# io.net
KiCad netlist of a schematic drawn in EAGLE
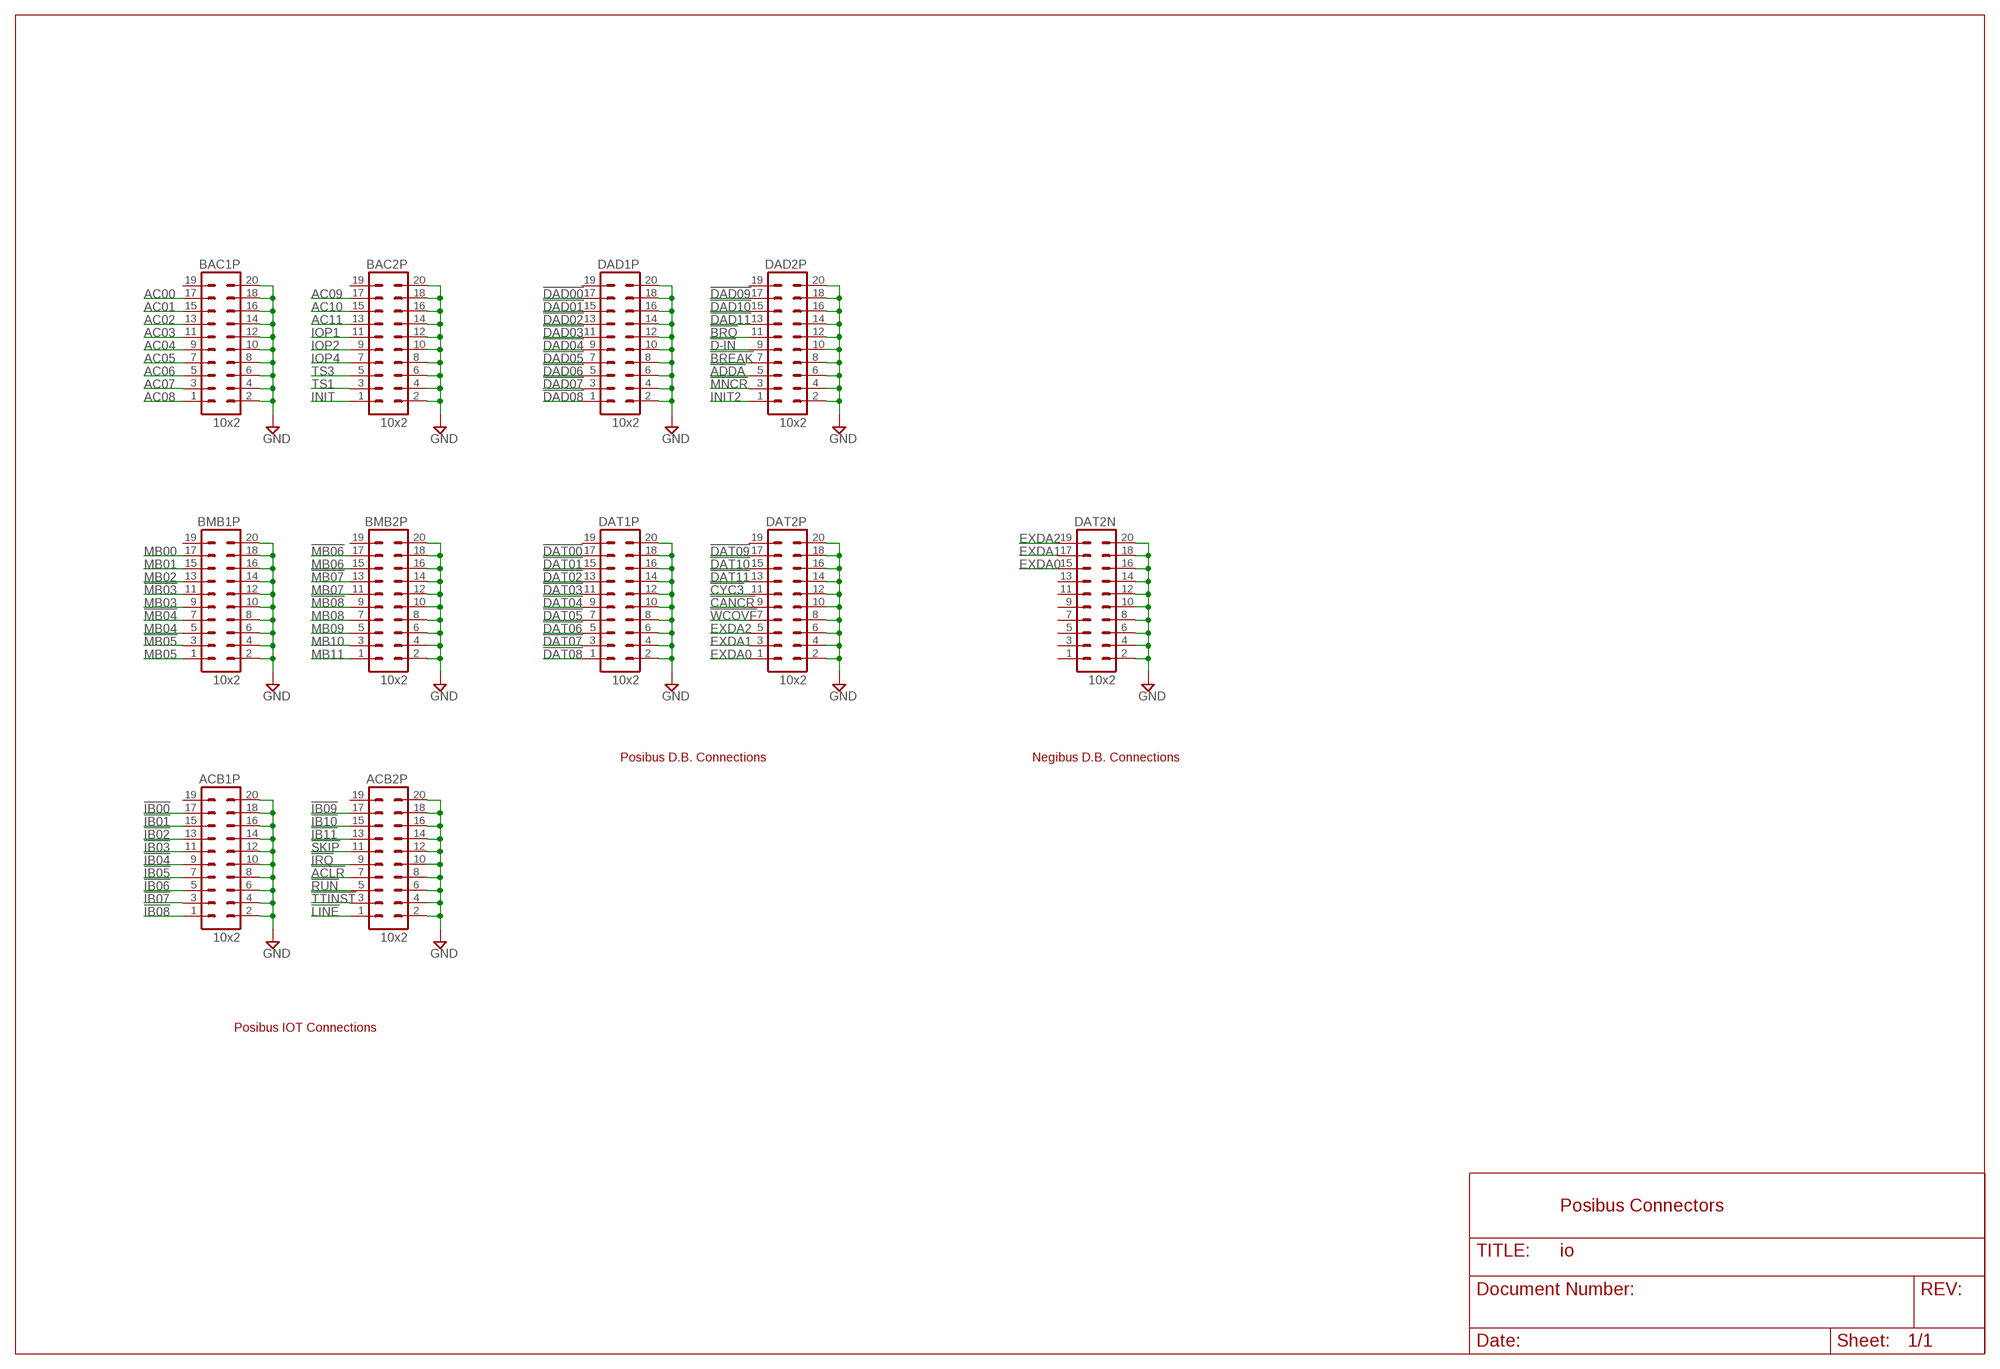
[diagram p0: schematic, sheet 1]

(export (version "E")
  (design (tool "Eeschema 10.0.6"))
  (components
    (comp (ref "ACB1P")
      (value "10x2")
      (footprint "eagle-import:MA10-2")
      (libsource (lib "eagle-import") (part "MA10-2"))
    )
    (comp (ref "ACB2P")
      (value "10x2")
      (footprint "eagle-import:MA10-2")
      (libsource (lib "eagle-import") (part "MA10-2"))
    )
    (comp (ref "BAC1P")
      (value "10x2")
      (footprint "eagle-import:MA10-2")
      (libsource (lib "eagle-import") (part "MA10-2"))
    )
    (comp (ref "BAC2P")
      (value "10x2")
      (footprint "eagle-import:MA10-2")
      (libsource (lib "eagle-import") (part "MA10-2"))
    )
    (comp (ref "BMB1P")
      (value "10x2")
      (footprint "eagle-import:MA10-2")
      (libsource (lib "eagle-import") (part "MA10-2"))
    )
    (comp (ref "BMB2P")
      (value "10x2")
      (footprint "eagle-import:MA10-2")
      (libsource (lib "eagle-import") (part "MA10-2"))
    )
    (comp (ref "DAD1P")
      (value "10x2")
      (footprint "eagle-import:MA10-2")
      (libsource (lib "eagle-import") (part "MA10-2"))
    )
    (comp (ref "DAD2P")
      (value "10x2")
      (footprint "eagle-import:MA10-2")
      (libsource (lib "eagle-import") (part "MA10-2"))
    )
    (comp (ref "DAT1P")
      (value "10x2")
      (footprint "eagle-import:MA10-2")
      (libsource (lib "eagle-import") (part "MA10-2"))
    )
    (comp (ref "DAT2N")
      (value "10x2")
      (footprint "eagle-import:MA10-2")
      (libsource (lib "eagle-import") (part "MA10-2"))
    )
    (comp (ref "DAT2P")
      (value "10x2")
      (footprint "eagle-import:MA10-2")
      (libsource (lib "eagle-import") (part "MA10-2"))
    )
  )
  (nets
    (net (code "1") (name "/AC00") (class "Default")
      (node (ref "BAC1P") (pin "17") (pinfunction "17_17") (pintype "passive"))
    )
    (net (code "2") (name "/AC01") (class "Default")
      (node (ref "BAC1P") (pin "15") (pinfunction "15_15") (pintype "passive"))
    )
    (net (code "3") (name "/AC02") (class "Default")
      (node (ref "BAC1P") (pin "13") (pinfunction "13_13") (pintype "passive"))
    )
    (net (code "4") (name "/AC03") (class "Default")
      (node (ref "BAC1P") (pin "11") (pinfunction "11_11") (pintype "passive"))
    )
    (net (code "5") (name "/AC04") (class "Default")
      (node (ref "BAC1P") (pin "9") (pinfunction "9_9") (pintype "passive"))
    )
    (net (code "6") (name "/AC05") (class "Default")
      (node (ref "BAC1P") (pin "7") (pinfunction "7_7") (pintype "passive"))
    )
    (net (code "7") (name "/AC06") (class "Default")
      (node (ref "BAC1P") (pin "5") (pinfunction "5_5") (pintype "passive"))
    )
    (net (code "8") (name "/AC07") (class "Default")
      (node (ref "BAC1P") (pin "3") (pinfunction "3_3") (pintype "passive"))
    )
    (net (code "9") (name "/AC08") (class "Default")
      (node (ref "BAC1P") (pin "1") (pinfunction "1_1") (pintype "passive"))
    )
    (net (code "10") (name "/AC09") (class "Default")
      (node (ref "BAC2P") (pin "17") (pinfunction "17_17") (pintype "passive"))
    )
    (net (code "11") (name "/AC10") (class "Default")
      (node (ref "BAC2P") (pin "15") (pinfunction "15_15") (pintype "passive"))
    )
    (net (code "12") (name "/AC11") (class "Default")
      (node (ref "BAC2P") (pin "13") (pinfunction "13_13") (pintype "passive"))
    )
    (net (code "13") (name "/EXDA0") (class "Default")
      (node (ref "DAT2N") (pin "15") (pinfunction "15_15") (pintype "passive"))
      (node (ref "DAT2P") (pin "1") (pinfunction "1_1") (pintype "passive"))
    )
    (net (code "14") (name "/EXDA1") (class "Default")
      (node (ref "DAT2N") (pin "17") (pinfunction "17_17") (pintype "passive"))
      (node (ref "DAT2P") (pin "3") (pinfunction "3_3") (pintype "passive"))
    )
    (net (code "15") (name "/EXDA2") (class "Default")
      (node (ref "DAT2N") (pin "19") (pinfunction "19_19") (pintype "passive"))
      (node (ref "DAT2P") (pin "5") (pinfunction "5_5") (pintype "passive"))
    )
    (net (code "16") (name "/INIT") (class "Default")
      (node (ref "BAC2P") (pin "1") (pinfunction "1_1") (pintype "passive"))
    )
    (net (code "17") (name "/INIT2") (class "Default")
      (node (ref "DAD2P") (pin "1") (pinfunction "1_1") (pintype "passive"))
    )
    (net (code "18") (name "/IOP1") (class "Default")
      (node (ref "BAC2P") (pin "11") (pinfunction "11_11") (pintype "passive"))
    )
    (net (code "19") (name "/IOP2") (class "Default")
      (node (ref "BAC2P") (pin "9") (pinfunction "9_9") (pintype "passive"))
    )
    (net (code "20") (name "/IOP4") (class "Default")
      (node (ref "BAC2P") (pin "7") (pinfunction "7_7") (pintype "passive"))
    )
    (net (code "21") (name "/MB00") (class "Default")
      (node (ref "BMB1P") (pin "17") (pinfunction "17_17") (pintype "passive"))
    )
    (net (code "22") (name "/MB01") (class "Default")
      (node (ref "BMB1P") (pin "15") (pinfunction "15_15") (pintype "passive"))
    )
    (net (code "23") (name "/MB02") (class "Default")
      (node (ref "BMB1P") (pin "13") (pinfunction "13_13") (pintype "passive"))
    )
    (net (code "24") (name "/MB03") (class "Default")
      (node (ref "BMB1P") (pin "9") (pinfunction "9_9") (pintype "passive"))
    )
    (net (code "25") (name "/MB04") (class "Default")
      (node (ref "BMB1P") (pin "5") (pinfunction "5_5") (pintype "passive"))
    )
    (net (code "26") (name "/MB05") (class "Default")
      (node (ref "BMB1P") (pin "1") (pinfunction "1_1") (pintype "passive"))
    )
    (net (code "27") (name "/MB06") (class "Default")
      (node (ref "BMB2P") (pin "15") (pinfunction "15_15") (pintype "passive"))
    )
    (net (code "28") (name "/MB07") (class "Default")
      (node (ref "BMB2P") (pin "11") (pinfunction "11_11") (pintype "passive"))
    )
    (net (code "29") (name "/MB08") (class "Default")
      (node (ref "BMB2P") (pin "7") (pinfunction "7_7") (pintype "passive"))
    )
    (net (code "30") (name "/MB09") (class "Default")
      (node (ref "BMB2P") (pin "5") (pinfunction "5_5") (pintype "passive"))
    )
    (net (code "31") (name "/MB10") (class "Default")
      (node (ref "BMB2P") (pin "3") (pinfunction "3_3") (pintype "passive"))
    )
    (net (code "32") (name "/MB11") (class "Default")
      (node (ref "BMB2P") (pin "1") (pinfunction "1_1") (pintype "passive"))
    )
    (net (code "33") (name "/TS1") (class "Default")
      (node (ref "BAC2P") (pin "3") (pinfunction "3_3") (pintype "passive"))
    )
    (net (code "34") (name "/TS3") (class "Default")
      (node (ref "BAC2P") (pin "5") (pinfunction "5_5") (pintype "passive"))
    )
    (net (code "35") (name "/~{ACLR}") (class "Default")
      (node (ref "ACB2P") (pin "7") (pinfunction "7_7") (pintype "passive"))
    )
    (net (code "36") (name "/~{ADDA}") (class "Default")
      (node (ref "DAD2P") (pin "5") (pinfunction "5_5") (pintype "passive"))
    )
    (net (code "37") (name "/~{BREAK}") (class "Default")
      (node (ref "DAD2P") (pin "7") (pinfunction "7_7") (pintype "passive"))
    )
    (net (code "38") (name "/~{BRQ}") (class "Default")
      (node (ref "DAD2P") (pin "11") (pinfunction "11_11") (pintype "passive"))
    )
    (net (code "39") (name "/~{CANCR}") (class "Default")
      (node (ref "DAT2P") (pin "9") (pinfunction "9_9") (pintype "passive"))
    )
    (net (code "40") (name "/~{CYC3}") (class "Default")
      (node (ref "DAT2P") (pin "11") (pinfunction "11_11") (pintype "passive"))
    )
    (net (code "41") (name "/~{D-IN}") (class "Default")
      (node (ref "DAD2P") (pin "9") (pinfunction "9_9") (pintype "passive"))
    )
    (net (code "42") (name "/~{DAD00}") (class "Default")
      (node (ref "DAD1P") (pin "17") (pinfunction "17_17") (pintype "passive"))
    )
    (net (code "43") (name "/~{DAD01}") (class "Default")
      (node (ref "DAD1P") (pin "15") (pinfunction "15_15") (pintype "passive"))
    )
    (net (code "44") (name "/~{DAD02}") (class "Default")
      (node (ref "DAD1P") (pin "13") (pinfunction "13_13") (pintype "passive"))
    )
    (net (code "45") (name "/~{DAD03}") (class "Default")
      (node (ref "DAD1P") (pin "11") (pinfunction "11_11") (pintype "passive"))
    )
    (net (code "46") (name "/~{DAD04}") (class "Default")
      (node (ref "DAD1P") (pin "9") (pinfunction "9_9") (pintype "passive"))
    )
    (net (code "47") (name "/~{DAD05}") (class "Default")
      (node (ref "DAD1P") (pin "7") (pinfunction "7_7") (pintype "passive"))
    )
    (net (code "48") (name "/~{DAD06}") (class "Default")
      (node (ref "DAD1P") (pin "5") (pinfunction "5_5") (pintype "passive"))
    )
    (net (code "49") (name "/~{DAD07}") (class "Default")
      (node (ref "DAD1P") (pin "3") (pinfunction "3_3") (pintype "passive"))
    )
    (net (code "50") (name "/~{DAD08}") (class "Default")
      (node (ref "DAD1P") (pin "1") (pinfunction "1_1") (pintype "passive"))
    )
    (net (code "51") (name "/~{DAD09}") (class "Default")
      (node (ref "DAD2P") (pin "17") (pinfunction "17_17") (pintype "passive"))
    )
    (net (code "52") (name "/~{DAD10}") (class "Default")
      (node (ref "DAD2P") (pin "15") (pinfunction "15_15") (pintype "passive"))
    )
    (net (code "53") (name "/~{DAD11}") (class "Default")
      (node (ref "DAD2P") (pin "13") (pinfunction "13_13") (pintype "passive"))
    )
    (net (code "54") (name "/~{DAT00}") (class "Default")
      (node (ref "DAT1P") (pin "17") (pinfunction "17_17") (pintype "passive"))
    )
    (net (code "55") (name "/~{DAT01}") (class "Default")
      (node (ref "DAT1P") (pin "15") (pinfunction "15_15") (pintype "passive"))
    )
    (net (code "56") (name "/~{DAT02}") (class "Default")
      (node (ref "DAT1P") (pin "13") (pinfunction "13_13") (pintype "passive"))
    )
    (net (code "57") (name "/~{DAT03}") (class "Default")
      (node (ref "DAT1P") (pin "11") (pinfunction "11_11") (pintype "passive"))
    )
    (net (code "58") (name "/~{DAT04}") (class "Default")
      (node (ref "DAT1P") (pin "9") (pinfunction "9_9") (pintype "passive"))
    )
    (net (code "59") (name "/~{DAT05}") (class "Default")
      (node (ref "DAT1P") (pin "7") (pinfunction "7_7") (pintype "passive"))
    )
    (net (code "60") (name "/~{DAT06}") (class "Default")
      (node (ref "DAT1P") (pin "5") (pinfunction "5_5") (pintype "passive"))
    )
    (net (code "61") (name "/~{DAT07}") (class "Default")
      (node (ref "DAT1P") (pin "3") (pinfunction "3_3") (pintype "passive"))
    )
    (net (code "62") (name "/~{DAT08}") (class "Default")
      (node (ref "DAT1P") (pin "1") (pinfunction "1_1") (pintype "passive"))
    )
    (net (code "63") (name "/~{DAT09}") (class "Default")
      (node (ref "DAT2P") (pin "17") (pinfunction "17_17") (pintype "passive"))
    )
    (net (code "64") (name "/~{DAT10}") (class "Default")
      (node (ref "DAT2P") (pin "15") (pinfunction "15_15") (pintype "passive"))
    )
    (net (code "65") (name "/~{DAT11}") (class "Default")
      (node (ref "DAT2P") (pin "13") (pinfunction "13_13") (pintype "passive"))
    )
    (net (code "66") (name "/~{IB00}") (class "Default")
      (node (ref "ACB1P") (pin "17") (pinfunction "17_17") (pintype "passive"))
    )
    (net (code "67") (name "/~{IB01}") (class "Default")
      (node (ref "ACB1P") (pin "15") (pinfunction "15_15") (pintype "passive"))
    )
    (net (code "68") (name "/~{IB02}") (class "Default")
      (node (ref "ACB1P") (pin "13") (pinfunction "13_13") (pintype "passive"))
    )
    (net (code "69") (name "/~{IB03}") (class "Default")
      (node (ref "ACB1P") (pin "11") (pinfunction "11_11") (pintype "passive"))
    )
    (net (code "70") (name "/~{IB04}") (class "Default")
      (node (ref "ACB1P") (pin "9") (pinfunction "9_9") (pintype "passive"))
    )
    (net (code "71") (name "/~{IB05}") (class "Default")
      (node (ref "ACB1P") (pin "7") (pinfunction "7_7") (pintype "passive"))
    )
    (net (code "72") (name "/~{IB06}") (class "Default")
      (node (ref "ACB1P") (pin "5") (pinfunction "5_5") (pintype "passive"))
    )
    (net (code "73") (name "/~{IB07}") (class "Default")
      (node (ref "ACB1P") (pin "3") (pinfunction "3_3") (pintype "passive"))
    )
    (net (code "74") (name "/~{IB08}") (class "Default")
      (node (ref "ACB1P") (pin "1") (pinfunction "1_1") (pintype "passive"))
    )
    (net (code "75") (name "/~{IB09}") (class "Default")
      (node (ref "ACB2P") (pin "17") (pinfunction "17_17") (pintype "passive"))
    )
    (net (code "76") (name "/~{IB10}") (class "Default")
      (node (ref "ACB2P") (pin "15") (pinfunction "15_15") (pintype "passive"))
    )
    (net (code "77") (name "/~{IB11}") (class "Default")
      (node (ref "ACB2P") (pin "13") (pinfunction "13_13") (pintype "passive"))
    )
    (net (code "78") (name "/~{IRQ}") (class "Default")
      (node (ref "ACB2P") (pin "9") (pinfunction "9_9") (pintype "passive"))
    )
    (net (code "79") (name "/~{LINE}") (class "Default")
      (node (ref "ACB2P") (pin "1") (pinfunction "1_1") (pintype "passive"))
    )
    (net (code "80") (name "/~{MB03}") (class "Default")
      (node (ref "BMB1P") (pin "11") (pinfunction "11_11") (pintype "passive"))
    )
    (net (code "81") (name "/~{MB04}") (class "Default")
      (node (ref "BMB1P") (pin "7") (pinfunction "7_7") (pintype "passive"))
    )
    (net (code "82") (name "/~{MB05}") (class "Default")
      (node (ref "BMB1P") (pin "3") (pinfunction "3_3") (pintype "passive"))
    )
    (net (code "83") (name "/~{MB06}") (class "Default")
      (node (ref "BMB2P") (pin "17") (pinfunction "17_17") (pintype "passive"))
    )
    (net (code "84") (name "/~{MB07}") (class "Default")
      (node (ref "BMB2P") (pin "13") (pinfunction "13_13") (pintype "passive"))
    )
    (net (code "85") (name "/~{MB08}") (class "Default")
      (node (ref "BMB2P") (pin "9") (pinfunction "9_9") (pintype "passive"))
    )
    (net (code "86") (name "/~{MNCR}") (class "Default")
      (node (ref "DAD2P") (pin "3") (pinfunction "3_3") (pintype "passive"))
    )
    (net (code "87") (name "/~{RUN}") (class "Default")
      (node (ref "ACB2P") (pin "5") (pinfunction "5_5") (pintype "passive"))
    )
    (net (code "88") (name "/~{SKIP}") (class "Default")
      (node (ref "ACB2P") (pin "11") (pinfunction "11_11") (pintype "passive"))
    )
    (net (code "89") (name "/~{TTINST}") (class "Default")
      (node (ref "ACB2P") (pin "3") (pinfunction "3_3") (pintype "passive"))
    )
    (net (code "90") (name "/~{WCOVF}") (class "Default")
      (node (ref "DAT2P") (pin "7") (pinfunction "7_7") (pintype "passive"))
    )
    (net (code "91") (name "GND") (class "Default")
      (node (ref "ACB1P") (pin "10") (pinfunction "10_10") (pintype "passive"))
      (node (ref "ACB1P") (pin "12") (pinfunction "12_12") (pintype "passive"))
      (node (ref "ACB1P") (pin "14") (pinfunction "14_14") (pintype "passive"))
      (node (ref "ACB1P") (pin "16") (pinfunction "16_16") (pintype "passive"))
      (node (ref "ACB1P") (pin "18") (pinfunction "18_18") (pintype "passive"))
      (node (ref "ACB1P") (pin "2") (pinfunction "2_2") (pintype "passive"))
      (node (ref "ACB1P") (pin "20") (pinfunction "20_20") (pintype "passive"))
      (node (ref "ACB1P") (pin "4") (pinfunction "4_4") (pintype "passive"))
      (node (ref "ACB1P") (pin "6") (pinfunction "6_6") (pintype "passive"))
      (node (ref "ACB1P") (pin "8") (pinfunction "8_8") (pintype "passive"))
      (node (ref "ACB2P") (pin "10") (pinfunction "10_10") (pintype "passive"))
      (node (ref "ACB2P") (pin "12") (pinfunction "12_12") (pintype "passive"))
      (node (ref "ACB2P") (pin "14") (pinfunction "14_14") (pintype "passive"))
      (node (ref "ACB2P") (pin "16") (pinfunction "16_16") (pintype "passive"))
      (node (ref "ACB2P") (pin "18") (pinfunction "18_18") (pintype "passive"))
      (node (ref "ACB2P") (pin "2") (pinfunction "2_2") (pintype "passive"))
      (node (ref "ACB2P") (pin "20") (pinfunction "20_20") (pintype "passive"))
      (node (ref "ACB2P") (pin "4") (pinfunction "4_4") (pintype "passive"))
      (node (ref "ACB2P") (pin "6") (pinfunction "6_6") (pintype "passive"))
      (node (ref "ACB2P") (pin "8") (pinfunction "8_8") (pintype "passive"))
      (node (ref "BAC1P") (pin "10") (pinfunction "10_10") (pintype "passive"))
      (node (ref "BAC1P") (pin "12") (pinfunction "12_12") (pintype "passive"))
      (node (ref "BAC1P") (pin "14") (pinfunction "14_14") (pintype "passive"))
      (node (ref "BAC1P") (pin "16") (pinfunction "16_16") (pintype "passive"))
      (node (ref "BAC1P") (pin "18") (pinfunction "18_18") (pintype "passive"))
      (node (ref "BAC1P") (pin "2") (pinfunction "2_2") (pintype "passive"))
      (node (ref "BAC1P") (pin "20") (pinfunction "20_20") (pintype "passive"))
      (node (ref "BAC1P") (pin "4") (pinfunction "4_4") (pintype "passive"))
      (node (ref "BAC1P") (pin "6") (pinfunction "6_6") (pintype "passive"))
      (node (ref "BAC1P") (pin "8") (pinfunction "8_8") (pintype "passive"))
      (node (ref "BAC2P") (pin "10") (pinfunction "10_10") (pintype "passive"))
      (node (ref "BAC2P") (pin "12") (pinfunction "12_12") (pintype "passive"))
      (node (ref "BAC2P") (pin "14") (pinfunction "14_14") (pintype "passive"))
      (node (ref "BAC2P") (pin "16") (pinfunction "16_16") (pintype "passive"))
      (node (ref "BAC2P") (pin "18") (pinfunction "18_18") (pintype "passive"))
      (node (ref "BAC2P") (pin "2") (pinfunction "2_2") (pintype "passive"))
      (node (ref "BAC2P") (pin "20") (pinfunction "20_20") (pintype "passive"))
      (node (ref "BAC2P") (pin "4") (pinfunction "4_4") (pintype "passive"))
      (node (ref "BAC2P") (pin "6") (pinfunction "6_6") (pintype "passive"))
      (node (ref "BAC2P") (pin "8") (pinfunction "8_8") (pintype "passive"))
      (node (ref "BMB1P") (pin "10") (pinfunction "10_10") (pintype "passive"))
      (node (ref "BMB1P") (pin "12") (pinfunction "12_12") (pintype "passive"))
      (node (ref "BMB1P") (pin "14") (pinfunction "14_14") (pintype "passive"))
      (node (ref "BMB1P") (pin "16") (pinfunction "16_16") (pintype "passive"))
      (node (ref "BMB1P") (pin "18") (pinfunction "18_18") (pintype "passive"))
      (node (ref "BMB1P") (pin "2") (pinfunction "2_2") (pintype "passive"))
      (node (ref "BMB1P") (pin "20") (pinfunction "20_20") (pintype "passive"))
      (node (ref "BMB1P") (pin "4") (pinfunction "4_4") (pintype "passive"))
      (node (ref "BMB1P") (pin "6") (pinfunction "6_6") (pintype "passive"))
      (node (ref "BMB1P") (pin "8") (pinfunction "8_8") (pintype "passive"))
      (node (ref "BMB2P") (pin "10") (pinfunction "10_10") (pintype "passive"))
      (node (ref "BMB2P") (pin "12") (pinfunction "12_12") (pintype "passive"))
      (node (ref "BMB2P") (pin "14") (pinfunction "14_14") (pintype "passive"))
      (node (ref "BMB2P") (pin "16") (pinfunction "16_16") (pintype "passive"))
      (node (ref "BMB2P") (pin "18") (pinfunction "18_18") (pintype "passive"))
      (node (ref "BMB2P") (pin "2") (pinfunction "2_2") (pintype "passive"))
      (node (ref "BMB2P") (pin "20") (pinfunction "20_20") (pintype "passive"))
      (node (ref "BMB2P") (pin "4") (pinfunction "4_4") (pintype "passive"))
      (node (ref "BMB2P") (pin "6") (pinfunction "6_6") (pintype "passive"))
      (node (ref "BMB2P") (pin "8") (pinfunction "8_8") (pintype "passive"))
      (node (ref "DAD1P") (pin "10") (pinfunction "10_10") (pintype "passive"))
      (node (ref "DAD1P") (pin "12") (pinfunction "12_12") (pintype "passive"))
      (node (ref "DAD1P") (pin "14") (pinfunction "14_14") (pintype "passive"))
      (node (ref "DAD1P") (pin "16") (pinfunction "16_16") (pintype "passive"))
      (node (ref "DAD1P") (pin "18") (pinfunction "18_18") (pintype "passive"))
      (node (ref "DAD1P") (pin "2") (pinfunction "2_2") (pintype "passive"))
      (node (ref "DAD1P") (pin "20") (pinfunction "20_20") (pintype "passive"))
      (node (ref "DAD1P") (pin "4") (pinfunction "4_4") (pintype "passive"))
      (node (ref "DAD1P") (pin "6") (pinfunction "6_6") (pintype "passive"))
      (node (ref "DAD1P") (pin "8") (pinfunction "8_8") (pintype "passive"))
      (node (ref "DAD2P") (pin "10") (pinfunction "10_10") (pintype "passive"))
      (node (ref "DAD2P") (pin "12") (pinfunction "12_12") (pintype "passive"))
      (node (ref "DAD2P") (pin "14") (pinfunction "14_14") (pintype "passive"))
      (node (ref "DAD2P") (pin "16") (pinfunction "16_16") (pintype "passive"))
      (node (ref "DAD2P") (pin "18") (pinfunction "18_18") (pintype "passive"))
      (node (ref "DAD2P") (pin "2") (pinfunction "2_2") (pintype "passive"))
      (node (ref "DAD2P") (pin "20") (pinfunction "20_20") (pintype "passive"))
      (node (ref "DAD2P") (pin "4") (pinfunction "4_4") (pintype "passive"))
      (node (ref "DAD2P") (pin "6") (pinfunction "6_6") (pintype "passive"))
      (node (ref "DAD2P") (pin "8") (pinfunction "8_8") (pintype "passive"))
      (node (ref "DAT1P") (pin "10") (pinfunction "10_10") (pintype "passive"))
      (node (ref "DAT1P") (pin "12") (pinfunction "12_12") (pintype "passive"))
      (node (ref "DAT1P") (pin "14") (pinfunction "14_14") (pintype "passive"))
      (node (ref "DAT1P") (pin "16") (pinfunction "16_16") (pintype "passive"))
      (node (ref "DAT1P") (pin "18") (pinfunction "18_18") (pintype "passive"))
      (node (ref "DAT1P") (pin "2") (pinfunction "2_2") (pintype "passive"))
      (node (ref "DAT1P") (pin "20") (pinfunction "20_20") (pintype "passive"))
      (node (ref "DAT1P") (pin "4") (pinfunction "4_4") (pintype "passive"))
      (node (ref "DAT1P") (pin "6") (pinfunction "6_6") (pintype "passive"))
      (node (ref "DAT1P") (pin "8") (pinfunction "8_8") (pintype "passive"))
      (node (ref "DAT2N") (pin "10") (pinfunction "10_10") (pintype "passive"))
      (node (ref "DAT2N") (pin "12") (pinfunction "12_12") (pintype "passive"))
      (node (ref "DAT2N") (pin "14") (pinfunction "14_14") (pintype "passive"))
      (node (ref "DAT2N") (pin "16") (pinfunction "16_16") (pintype "passive"))
      (node (ref "DAT2N") (pin "18") (pinfunction "18_18") (pintype "passive"))
      (node (ref "DAT2N") (pin "2") (pinfunction "2_2") (pintype "passive"))
      (node (ref "DAT2N") (pin "20") (pinfunction "20_20") (pintype "passive"))
      (node (ref "DAT2N") (pin "4") (pinfunction "4_4") (pintype "passive"))
      (node (ref "DAT2N") (pin "6") (pinfunction "6_6") (pintype "passive"))
      (node (ref "DAT2N") (pin "8") (pinfunction "8_8") (pintype "passive"))
      (node (ref "DAT2P") (pin "10") (pinfunction "10_10") (pintype "passive"))
      (node (ref "DAT2P") (pin "12") (pinfunction "12_12") (pintype "passive"))
      (node (ref "DAT2P") (pin "14") (pinfunction "14_14") (pintype "passive"))
      (node (ref "DAT2P") (pin "16") (pinfunction "16_16") (pintype "passive"))
      (node (ref "DAT2P") (pin "18") (pinfunction "18_18") (pintype "passive"))
      (node (ref "DAT2P") (pin "2") (pinfunction "2_2") (pintype "passive"))
      (node (ref "DAT2P") (pin "20") (pinfunction "20_20") (pintype "passive"))
      (node (ref "DAT2P") (pin "4") (pinfunction "4_4") (pintype "passive"))
      (node (ref "DAT2P") (pin "6") (pinfunction "6_6") (pintype "passive"))
      (node (ref "DAT2P") (pin "8") (pinfunction "8_8") (pintype "passive"))
    )
    (net (code "92") (name "unconnected-(ACB1P-Pad19)") (class "Default")
      (node (ref "ACB1P") (pin "19") (pinfunction "19_19") (pintype "passive"))
    )
    (net (code "93") (name "unconnected-(ACB2P-Pad19)") (class "Default")
      (node (ref "ACB2P") (pin "19") (pinfunction "19_19") (pintype "passive"))
    )
    (net (code "94") (name "unconnected-(BAC1P-Pad19)") (class "Default")
      (node (ref "BAC1P") (pin "19") (pinfunction "19_19") (pintype "passive"))
    )
    (net (code "95") (name "unconnected-(BAC2P-Pad19)") (class "Default")
      (node (ref "BAC2P") (pin "19") (pinfunction "19_19") (pintype "passive"))
    )
    (net (code "96") (name "unconnected-(BMB1P-Pad19)") (class "Default")
      (node (ref "BMB1P") (pin "19") (pinfunction "19_19") (pintype "passive"))
    )
    (net (code "97") (name "unconnected-(BMB2P-Pad19)") (class "Default")
      (node (ref "BMB2P") (pin "19") (pinfunction "19_19") (pintype "passive"))
    )
    (net (code "98") (name "unconnected-(DAD1P-Pad19)") (class "Default")
      (node (ref "DAD1P") (pin "19") (pinfunction "19_19") (pintype "passive"))
    )
    (net (code "99") (name "unconnected-(DAD2P-Pad19)") (class "Default")
      (node (ref "DAD2P") (pin "19") (pinfunction "19_19") (pintype "passive"))
    )
    (net (code "100") (name "unconnected-(DAT1P-Pad19)") (class "Default")
      (node (ref "DAT1P") (pin "19") (pinfunction "19_19") (pintype "passive"))
    )
    (net (code "101") (name "unconnected-(DAT2N-Pad1)") (class "Default")
      (node (ref "DAT2N") (pin "1") (pinfunction "1_1") (pintype "passive"))
    )
    (net (code "102") (name "unconnected-(DAT2N-Pad3)") (class "Default")
      (node (ref "DAT2N") (pin "3") (pinfunction "3_3") (pintype "passive"))
    )
    (net (code "103") (name "unconnected-(DAT2N-Pad5)") (class "Default")
      (node (ref "DAT2N") (pin "5") (pinfunction "5_5") (pintype "passive"))
    )
    (net (code "104") (name "unconnected-(DAT2N-Pad7)") (class "Default")
      (node (ref "DAT2N") (pin "7") (pinfunction "7_7") (pintype "passive"))
    )
    (net (code "105") (name "unconnected-(DAT2N-Pad9)") (class "Default")
      (node (ref "DAT2N") (pin "9") (pinfunction "9_9") (pintype "passive"))
    )
    (net (code "106") (name "unconnected-(DAT2N-Pad11)") (class "Default")
      (node (ref "DAT2N") (pin "11") (pinfunction "11_11") (pintype "passive"))
    )
    (net (code "107") (name "unconnected-(DAT2N-Pad13)") (class "Default")
      (node (ref "DAT2N") (pin "13") (pinfunction "13_13") (pintype "passive"))
    )
    (net (code "108") (name "unconnected-(DAT2P-Pad19)") (class "Default")
      (node (ref "DAT2P") (pin "19") (pinfunction "19_19") (pintype "passive"))
    )
  )
)
